# Automatic_Night_Light.net
KiCad netlist of a schematic drawn in EAGLE
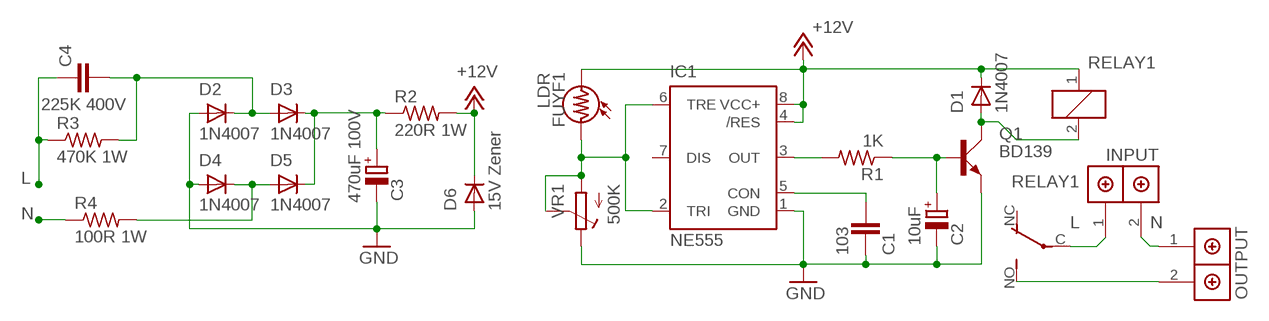
[diagram p0: schematic, sheet 1]

(export (version "E")
  (design (tool "Eeschema 10.0.6"))
  (components
    (comp (ref "C1")
      (value "103")
      (footprint "eagle-import:104")
      (libsource (lib "eagle-import") (part "104"))
    )
    (comp (ref "C2")
      (value "10uF")
      (footprint "eagle-import:10UF_50V")
      (libsource (lib "eagle-import") (part "10UF"))
    )
    (comp (ref "C3")
      (value "470uF 100V")
      (footprint "eagle-import:1000UF_16V")
      (libsource (lib "eagle-import") (part "470UF/16V"))
    )
    (comp (ref "C4")
      (value "225K 400V")
      (footprint "eagle-import:C150-091X182")
      (libsource (lib "eagle-import") (part "C-EU150-091X182"))
    )
    (comp (ref "D1")
      (value "1N4007")
      (footprint "eagle-import:1N4007_V2")
      (libsource (lib "eagle-import") (part "1N4007204/7"))
    )
    (comp (ref "D2")
      (value "1N4007")
      (footprint "eagle-import:1N4007_V2")
      (libsource (lib "eagle-import") (part "1N4007204/7"))
    )
    (comp (ref "D3")
      (value "1N4007")
      (footprint "eagle-import:1N4007_V2")
      (libsource (lib "eagle-import") (part "1N4007204/7"))
    )
    (comp (ref "D4")
      (value "1N4007")
      (footprint "eagle-import:1N4007_V2")
      (libsource (lib "eagle-import") (part "1N4007204/7"))
    )
    (comp (ref "D5")
      (value "1N4007")
      (footprint "eagle-import:1N4007_V2")
      (libsource (lib "eagle-import") (part "1N4007204/7"))
    )
    (comp (ref "D6")
      (value "15V Zener")
      (footprint "eagle-import:1N4007_V2")
      (libsource (lib "eagle-import") (part "1N4007204/7"))
    )
    (comp (ref "FUYF1")
      (value "LDR")
      (footprint "eagle-import:LDR")
      (libsource (lib "eagle-import") (part "LDR"))
    )
    (comp (ref "IC1")
      (value "NE555")
      (footprint "eagle-import:DIL-08")
      (fields (field (name "MF") "Arrow Electronics") (field (name "MPN") "NE555N"))
      (libsource (lib "eagle-import") (part "NE555"))
    )
    (comp (ref "INPUT")
      (value "INPUT")
      (footprint "eagle-import:2P")
      (libsource (lib "eagle-import") (part "2P"))
    )
    (comp (ref "OUTPUT")
      (value "2P")
      (footprint "eagle-import:2P")
      (libsource (lib "eagle-import") (part "2P"))
    )
    (comp (ref "Q1")
      (value "BD139")
      (footprint "eagle-import:TO126AV")
      (libsource (lib "eagle-import") (part "BD139"))
    )
    (comp (ref "R1")
      (value "1K")
      (footprint "eagle-import:THR_R_204_7")
      (libsource (lib "eagle-import") (part "RES204/7"))
    )
    (comp (ref "R2")
      (value "220R 1W")
      (footprint "eagle-import:1_2W")
      (libsource (lib "eagle-import") (part "1/2W"))
    )
    (comp (ref "R3")
      (value "470K 1W")
      (footprint "eagle-import:1_2W")
      (libsource (lib "eagle-import") (part "1/2W"))
    )
    (comp (ref "R4")
      (value "100R 1W")
      (footprint "eagle-import:1_2W")
      (libsource (lib "eagle-import") (part "1/2W"))
    )
    (comp (ref "RELAY1")
      (value "RELAY")
      (footprint "eagle-import:RELAY")
      (libsource (lib "eagle-import") (part "RELAY"))
    )
    (comp (ref "VR1")
      (value "500K")
      (footprint "eagle-import:BLUE_VR")
      (libsource (lib "eagle-import") (part "BLUE_VR"))
    )
  )
  (nets
    (net (code "1") (name "+12V") (class "Default")
      (node (ref "D1") (pin "C") (pinfunction "C_C") (pintype "passive"))
      (node (ref "D6") (pin "C") (pinfunction "C_C") (pintype "passive"))
      (node (ref "FUYF1") (pin "3") (pinfunction "P$2_3") (pintype "bidirectional"))
      (node (ref "IC1") (pin "4") (pinfunction "/RES_4") (pintype "input"))
      (node (ref "IC1") (pin "8") (pinfunction "VCC+_8") (pintype "power_in"))
      (node (ref "R2") (pin "2") (pinfunction "2_2") (pintype "passive"))
      (node (ref "RELAY1") (pin "1") (pinfunction "1_1") (pintype "passive"))
    )
    (net (code "2") (name "/L") (class "Default")
      (node (ref "C4") (pin "1") (pinfunction "1_1") (pintype "passive"))
      (node (ref "INPUT") (pin "1") (pinfunction "CONN1_1") (pintype "bidirectional"))
      (node (ref "R3") (pin "1") (pinfunction "1_1") (pintype "passive"))
      (node (ref "RELAY1") (pin "C") (pinfunction "C_C") (pintype "passive"))
    )
    (net (code "3") (name "/N") (class "Default")
      (node (ref "INPUT") (pin "2") (pinfunction "CONN2_2") (pintype "bidirectional"))
      (node (ref "OUTPUT") (pin "1") (pinfunction "CONN1_1") (pintype "bidirectional"))
      (node (ref "R4") (pin "1") (pinfunction "1_1") (pintype "passive"))
    )
    (net (code "4") (name "GND") (class "Default")
      (node (ref "C1") (pin "2") (pinfunction "2_2") (pintype "passive"))
      (node (ref "C2") (pin "-") (pinfunction "-_-") (pintype "passive"))
      (node (ref "C3") (pin "-") (pinfunction "-_-") (pintype "passive"))
      (node (ref "D2") (pin "A") (pinfunction "A_A") (pintype "passive"))
      (node (ref "D4") (pin "A") (pinfunction "A_A") (pintype "passive"))
      (node (ref "D6") (pin "A") (pinfunction "A_A") (pintype "passive"))
      (node (ref "IC1") (pin "1") (pinfunction "GND_1") (pintype "power_in"))
      (node (ref "Q1") (pin "E") (pinfunction "E_E") (pintype "passive"))
      (node (ref "VR1") (pin "1") (pinfunction "1_1") (pintype "bidirectional"))
    )
    (net (code "5") (name "Net-(C2-Pad+)") (class "Default")
      (node (ref "C2") (pin "+") (pinfunction "+_+") (pintype "passive"))
      (node (ref "Q1") (pin "B") (pinfunction "B_B") (pintype "passive"))
      (node (ref "R1") (pin "1") (pinfunction "1_1") (pintype "passive"))
    )
    (net (code "6") (name "Net-(C3-Pad+)") (class "Default")
      (node (ref "C3") (pin "+") (pinfunction "+_+") (pintype "passive"))
      (node (ref "D3") (pin "C") (pinfunction "C_C") (pintype "passive"))
      (node (ref "D5") (pin "C") (pinfunction "C_C") (pintype "passive"))
      (node (ref "R2") (pin "1") (pinfunction "1_1") (pintype "passive"))
    )
    (net (code "7") (name "Net-(C4-Pad2)") (class "Default")
      (node (ref "C4") (pin "2") (pinfunction "2_2") (pintype "passive"))
      (node (ref "D2") (pin "C") (pinfunction "C_C") (pintype "passive"))
      (node (ref "D3") (pin "A") (pinfunction "A_A") (pintype "passive"))
      (node (ref "R3") (pin "2") (pinfunction "2_2") (pintype "passive"))
    )
    (net (code "8") (name "Net-(D1-PadA)") (class "Default")
      (node (ref "D1") (pin "A") (pinfunction "A_A") (pintype "passive"))
      (node (ref "Q1") (pin "C") (pinfunction "C_C") (pintype "passive"))
      (node (ref "RELAY1") (pin "2") (pinfunction "2_2") (pintype "passive"))
    )
    (net (code "9") (name "Net-(D4-PadC)") (class "Default")
      (node (ref "D4") (pin "C") (pinfunction "C_C") (pintype "passive"))
      (node (ref "D5") (pin "A") (pinfunction "A_A") (pintype "passive"))
      (node (ref "R4") (pin "2") (pinfunction "2_2") (pintype "passive"))
    )
    (net (code "10") (name "Net-(FUYF1-P$1)") (class "Default")
      (node (ref "FUYF1") (pin "1") (pinfunction "P$1_1") (pintype "bidirectional"))
      (node (ref "IC1") (pin "2") (pinfunction "TRI_2") (pintype "input"))
      (node (ref "IC1") (pin "6") (pinfunction "TRE_6") (pintype "input"))
      (node (ref "VR1") (pin "2") (pinfunction "2_2") (pintype "bidirectional"))
      (node (ref "VR1") (pin "3") (pinfunction "3_3") (pintype "bidirectional"))
    )
    (net (code "11") (name "Net-(IC1-CON)") (class "Default")
      (node (ref "C1") (pin "1") (pinfunction "1_1") (pintype "passive"))
      (node (ref "IC1") (pin "5") (pinfunction "CON_5") (pintype "input"))
    )
    (net (code "12") (name "Net-(IC1-OUT)") (class "Default")
      (node (ref "IC1") (pin "3") (pinfunction "OUT_3") (pintype "output"))
      (node (ref "R1") (pin "2") (pinfunction "2_2") (pintype "passive"))
    )
    (net (code "13") (name "Net-(OUTPUT-CONN2)") (class "Default")
      (node (ref "OUTPUT") (pin "2") (pinfunction "CONN2_2") (pintype "bidirectional"))
      (node (ref "RELAY1") (pin "NO") (pinfunction "NO_NO") (pintype "passive"))
    )
    (net (code "14") (name "unconnected-(IC1-DIS-Pad7)") (class "Default")
      (node (ref "IC1") (pin "7") (pinfunction "DIS_7") (pintype "input"))
    )
    (net (code "15") (name "unconnected-(RELAY1-PadNC)") (class "Default")
      (node (ref "RELAY1") (pin "NC") (pinfunction "NC_NC") (pintype "passive"))
    )
  )
)
